# Control_Panel_Power.net
KiCad netlist of a schematic drawn in Altium Designer
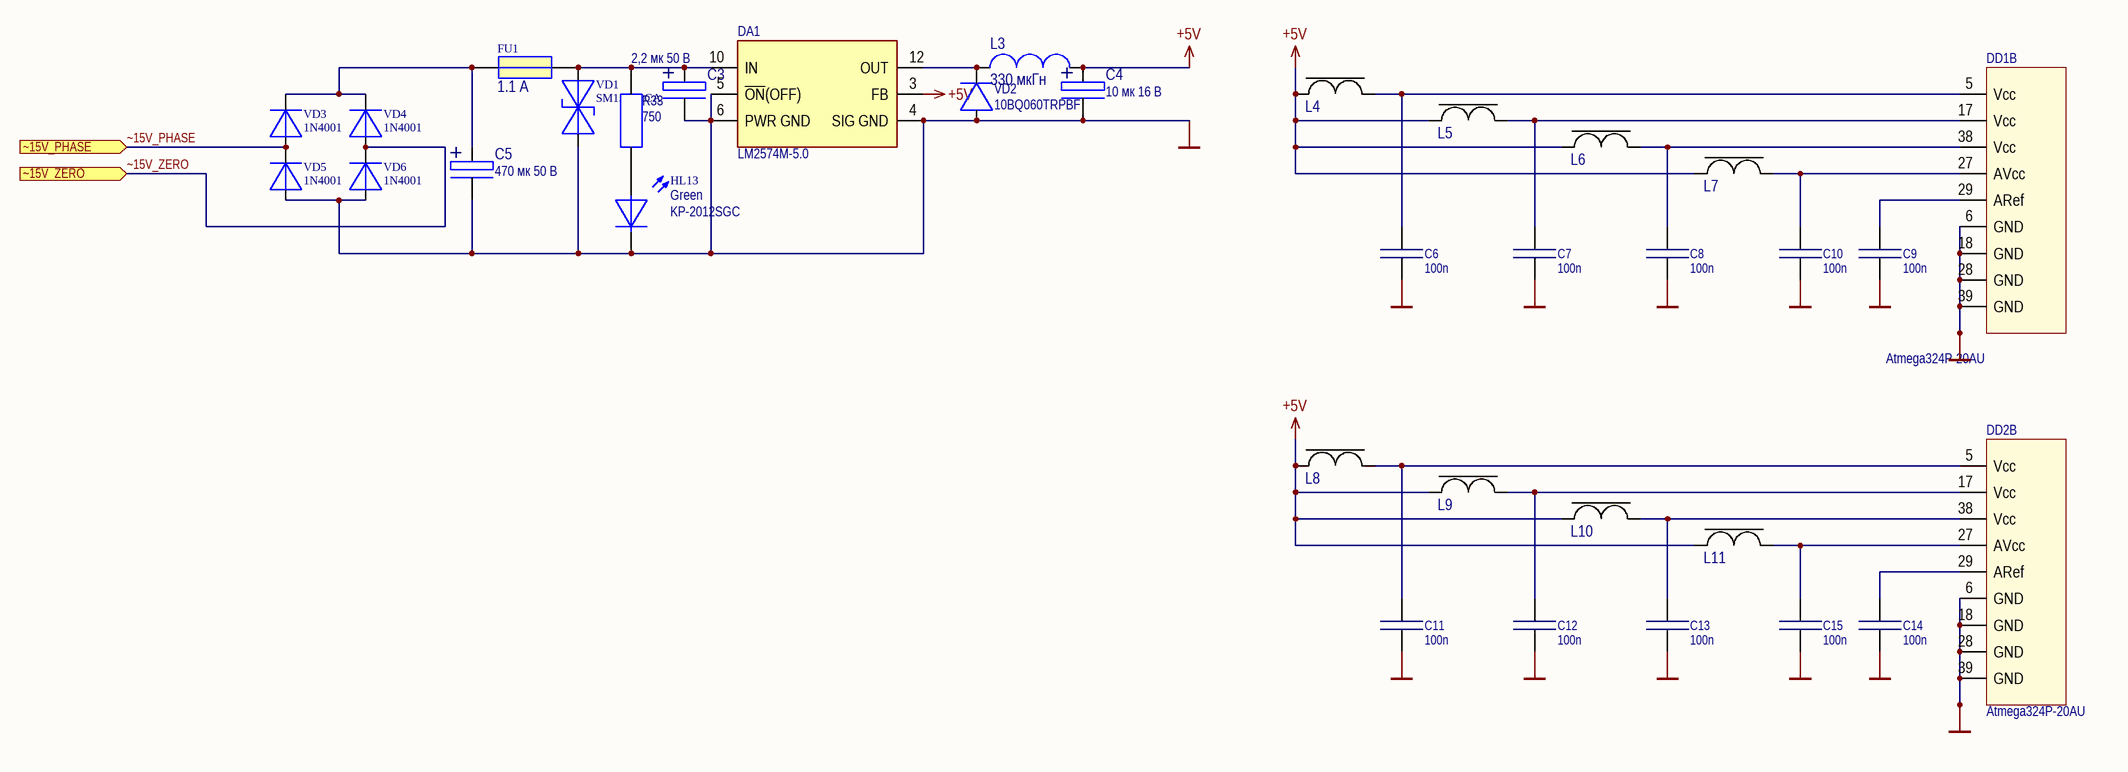
[diagram p0: Control_Panel_Power.SchDoc]

(export (version "E")
  (design (tool "Eeschema 10.0.6"))
  (components
    (comp (ref "C3")
      (value "2,2 мк 50 В")
      (footprint "Cap:CAP_POLAR_ELLYTE_B")
      (description "2,2uF 50V Polar capacitor")
      (fields
        (field (name "MANUFACTURERPARTNUMBER") "CA050M2R20REB-0405")
        (field (name "MANUFACTURER") "Yageo")
      )
      (libsource (lib "Cap") (part "02200_050"))
    )
    (comp (ref "C4")
      (value "10 мк 16 В")
      (footprint "Cap:CAP_POLAR_ELLYTE_B")
      (description "10uF 16V Polar SMD cap")
      (fields
        (field (name "MANUFACTURERPARTNUMBER") "CA016M0010REB-0405")
        (field (name "MANUFACTURER") "YAGEO")
      )
      (libsource (lib "Cap") (part "10000_016"))
    )
    (comp (ref "C5")
      (value "470 мк 50 В")
      (footprint "Cap:CAP_POLAR_10mm")
      (description "470uF 50V Polar capacitor")
      (fields (field (name "MANUFACTURERPARTNUMBER") "CA035M0220REG") (field (name "MANUFACTURER") "Yageo"))
      (libsource (lib "Cap") (part "470000_050"))
    )
    (comp (ref "C6")
      (value "100n")
      (footprint "SMDRC0805")
      (description "Generic capasitor non-polar")
      (fields (field (name "PARTNUMBER") "Capacitor 0805 100n"))
      (libsource (lib "library") (part "Capacitor"))
    )
    (comp (ref "C7")
      (value "100n")
      (footprint "SMDRC0805")
      (description "Generic capasitor non-polar")
      (fields (field (name "PARTNUMBER") "Capacitor 0805 100n"))
      (libsource (lib "library") (part "Capacitor"))
    )
    (comp (ref "C8")
      (value "100n")
      (footprint "SMDRC0805")
      (description "Generic capasitor non-polar")
      (fields (field (name "PARTNUMBER") "Capacitor 0805 100n"))
      (libsource (lib "library") (part "Capacitor"))
    )
    (comp (ref "C9")
      (value "100n")
      (footprint "SMDRC0805")
      (description "Generic capasitor non-polar")
      (fields (field (name "PARTNUMBER") "Capacitor 0805 100n"))
      (libsource (lib "library") (part "Capacitor"))
    )
    (comp (ref "C10")
      (value "100n")
      (footprint "SMDRC0805")
      (description "Generic capasitor non-polar")
      (fields (field (name "PARTNUMBER") "Capacitor 0805 100n"))
      (libsource (lib "library") (part "Capacitor"))
    )
    (comp (ref "C11")
      (value "100n")
      (footprint "SMDRC0805")
      (description "Generic capasitor non-polar")
      (fields (field (name "PARTNUMBER") "Capacitor 0805 100n"))
      (libsource (lib "library") (part "Capacitor"))
    )
    (comp (ref "C12")
      (value "100n")
      (footprint "SMDRC0805")
      (description "Generic capasitor non-polar")
      (fields (field (name "PARTNUMBER") "Capacitor 0805 100n"))
      (libsource (lib "library") (part "Capacitor"))
    )
    (comp (ref "C13")
      (value "100n")
      (footprint "SMDRC0805")
      (description "Generic capasitor non-polar")
      (fields (field (name "PARTNUMBER") "Capacitor 0805 100n"))
      (libsource (lib "library") (part "Capacitor"))
    )
    (comp (ref "C14")
      (value "100n")
      (footprint "SMDRC0805")
      (description "Generic capasitor non-polar")
      (fields (field (name "PARTNUMBER") "Capacitor 0805 100n"))
      (libsource (lib "library") (part "Capacitor"))
    )
    (comp (ref "C15")
      (value "100n")
      (footprint "SMDRC0805")
      (description "Generic capasitor non-polar")
      (fields (field (name "PARTNUMBER") "Capacitor 0805 100n"))
      (libsource (lib "library") (part "Capacitor"))
    )
    (comp (ref "DA1")
      (value "LM2574M-5.0")
      (footprint "Power:SOIC127P1030X264-14M")
      (fields (field (name "MANUFACTURERPARTNUMBER") "LM2574M-5.0"))
      (libsource (lib "Power") (part "LM2574M-5.0"))
    )
    (comp (ref "DD1")
      (value "Atmega324P-20AU")
      (footprint "Atmel Microcontroller 8-Bit Automotive AVR:44ML_M")
      (description "Microcontroller 8-bit")
      (fields (field (name "MANUFACTURER") "Atmel") (field (name "MANUFACTURERPARTNUMBER") "Atmega324P-20AU"))
      (libsource (lib "Microcontrollers") (part "Atmega324P-20AU"))
    )
    (comp (ref "DD2")
      (value "Atmega324P-20AU")
      (footprint "Atmel Microcontroller 8-Bit Automotive AVR:44ML_M")
      (description "Microcontroller 8-bit")
      (fields (field (name "MANUFACTURER") "Atmel") (field (name "MANUFACTURERPARTNUMBER") "Atmega324P-20AU"))
      (libsource (lib "Microcontrollers") (part "Atmega324P-20AU"))
    )
    (comp (ref "FU1")
      (value "1.1 А")
      (footprint "Power:EFuse 1.1A")
      (description "Fuse")
      (fields (field (name "MANUFACTURERPARTNUMBER") "EFuse LP60-110F"))
      (libsource (lib "Power") (part "EFuse LP60-110F"))
    )
    (comp (ref "HL13")
      (value "Green")
      (footprint "Indicator:DIOMELF2012M")
      (description "Diod LED SMD Green")
      (fields (field (name "MANUFACTURERPARTNUMBER") "KP-2012SGC"))
      (libsource (lib "Indicator") (part "LED1_G"))
    )
    (comp (ref "L3")
      (value "330 мкГн")
      (footprint "Inductor:INDP7972X50M")
      (description "Inductor")
      (fields (field (name "MANUFACTURERPARTNUMBER") "SCD0705T-331K-N"))
      (libsource (lib "Inductor") (part "SCD0705T-331K-N"))
    )
    (comp (ref "L4")
      (value "MPZ1608S181A")
      (footprint "Inductor:INDC0603X03M")
      (description "Ferrite Bead")
      (libsource (lib "Inductor") (part "Ferrite Bead"))
    )
    (comp (ref "L5")
      (value "MPZ1608S181A")
      (footprint "Inductor:INDC0603X03M")
      (description "Ferrite Bead")
      (libsource (lib "Inductor") (part "Ferrite Bead"))
    )
    (comp (ref "L6")
      (value "MPZ1608S181A")
      (footprint "Inductor:INDC0603X03M")
      (description "Ferrite Bead")
      (libsource (lib "Inductor") (part "Ferrite Bead"))
    )
    (comp (ref "L7")
      (value "MPZ1608S181A")
      (footprint "Inductor:INDC0603X03M")
      (description "Ferrite Bead")
      (libsource (lib "Inductor") (part "Ferrite Bead"))
    )
    (comp (ref "L8")
      (value "MPZ1608S181A")
      (footprint "Inductor:INDC0603X03M")
      (description "Ferrite Bead")
      (libsource (lib "Inductor") (part "Ferrite Bead"))
    )
    (comp (ref "L9")
      (value "MPZ1608S181A")
      (footprint "Inductor:INDC0603X03M")
      (description "Ferrite Bead")
      (libsource (lib "Inductor") (part "Ferrite Bead"))
    )
    (comp (ref "L10")
      (value "MPZ1608S181A")
      (footprint "Inductor:INDC0603X03M")
      (description "Ferrite Bead")
      (libsource (lib "Inductor") (part "Ferrite Bead"))
    )
    (comp (ref "L11")
      (value "MPZ1608S181A")
      (footprint "Inductor:INDC0603X03M")
      (description "Ferrite Bead")
      (libsource (lib "Inductor") (part "Ferrite Bead"))
    )
    (comp (ref "R33")
      (value "750")
      (footprint "SMDRC0805")
      (description "Generic resistor")
      (fields (field (name "PARTNUMBER") "Resistor 0805 750"))
      (libsource (lib "library") (part "Resistor"))
    )
    (comp (ref "VD1")
      (value "SM15T12CA")
      (footprint "DIod:SUPRES3216X18N")
      (description "Diod suppressor")
      (fields
        (field (name "MANUFACTURER") "ST Microelectronics")
        (field (name "MANUFACTURERPARTNUMBER") "SM15T12CA")
      )
      (libsource (lib "Diod") (part "SM15T12CA"))
    )
    (comp (ref "VD2")
      (value "10BQ060TRPBF")
      (footprint "DIod:SHOTKY 4.1x3.3")
      (description "DIODE SCHOTTKY 60V 1A DO214AA")
      (fields
        (field (name "MANUFACTURER") "Vishay Semiconductor Diodes Division")
        (field (name "MANUFACTURERPARTNUMBER") "10BQ060TRPBF")
      )
      (libsource (lib "Diod") (part "10BQ060TRPBF"))
    )
    (comp (ref "VD3")
      (value "1N4001")
      (footprint "DIod:PinDiode")
      (description "Rectifying diode")
      (fields (field (name "MANUFACTURERPARTNUMBER") "1N4001"))
      (libsource (lib "Diod") (part "1N4001"))
    )
    (comp (ref "VD4")
      (value "1N4001")
      (footprint "DIod:PinDiode")
      (description "Rectifying diode")
      (fields (field (name "MANUFACTURERPARTNUMBER") "1N4001"))
      (libsource (lib "Diod") (part "1N4001"))
    )
    (comp (ref "VD5")
      (value "1N4001")
      (footprint "DIod:PinDiode")
      (description "Rectifying diode")
      (fields (field (name "MANUFACTURERPARTNUMBER") "1N4001"))
      (libsource (lib "Diod") (part "1N4001"))
    )
    (comp (ref "VD6")
      (value "1N4001")
      (footprint "DIod:PinDiode")
      (description "Rectifying diode")
      (fields (field (name "MANUFACTURERPARTNUMBER") "1N4001"))
      (libsource (lib "Diod") (part "1N4001"))
    )
  )
  (nets
    (net (code "1") (name "+5V") (class "Default")
      (node (ref "C4") (pin "2") (pinfunction "+_2") (pintype "passive"))
      (node (ref "DA1") (pin "3") (pinfunction "FB_3") (pintype "passive"))
      (node (ref "L10") (pin "1") (pinfunction "1_1") (pintype "passive"))
      (node (ref "L11") (pin "1") (pinfunction "1_1") (pintype "passive"))
      (node (ref "L3") (pin "1") (pinfunction "1_1") (pintype "passive"))
      (node (ref "L4") (pin "1") (pinfunction "1_1") (pintype "passive"))
      (node (ref "L5") (pin "1") (pinfunction "1_1") (pintype "passive"))
      (node (ref "L6") (pin "1") (pinfunction "1_1") (pintype "passive"))
      (node (ref "L7") (pin "1") (pinfunction "1_1") (pintype "passive"))
      (node (ref "L8") (pin "1") (pinfunction "1_1") (pintype "passive"))
      (node (ref "L9") (pin "1") (pinfunction "1_1") (pintype "passive"))
    )
    (net (code "2") (name "/~15V_PHASE") (class "Default")
      (node (ref "VD3") (pin "A") (pinfunction "A_A") (pintype "passive"))
      (node (ref "VD5") (pin "K") (pinfunction "K_K") (pintype "passive"))
    )
    (net (code "3") (name "/~15V_ZERO") (class "Default")
      (node (ref "VD4") (pin "A") (pinfunction "A_A") (pintype "passive"))
      (node (ref "VD6") (pin "K") (pinfunction "K_K") (pintype "passive"))
    )
    (net (code "4") (name "GND") (class "Default")
      (node (ref "C10") (pin "1") (pintype "passive"))
      (node (ref "C11") (pin "2") (pintype "passive"))
      (node (ref "C12") (pin "2") (pintype "passive"))
      (node (ref "C13") (pin "2") (pintype "passive"))
      (node (ref "C14") (pin "2") (pintype "passive"))
      (node (ref "C15") (pin "1") (pintype "passive"))
      (node (ref "C3") (pin "1") (pinfunction "-_1") (pintype "passive"))
      (node (ref "C4") (pin "1") (pinfunction "-_1") (pintype "passive"))
      (node (ref "C5") (pin "1") (pinfunction "-_1") (pintype "passive"))
      (node (ref "C6") (pin "2") (pintype "passive"))
      (node (ref "C7") (pin "2") (pintype "passive"))
      (node (ref "C8") (pin "2") (pintype "passive"))
      (node (ref "C9") (pin "2") (pintype "passive"))
      (node (ref "DA1") (pin "4") (pinfunction "SIG_GND_4") (pintype "passive"))
      (node (ref "DA1") (pin "5") (pinfunction "~{ON}(OFF)_5") (pintype "passive"))
      (node (ref "DA1") (pin "6") (pinfunction "PWR_GND_6") (pintype "passive"))
      (node (ref "DD1") (pin "18") (pinfunction "GND_18") (pintype "power_in"))
      (node (ref "DD1") (pin "28") (pinfunction "GND_28") (pintype "power_in"))
      (node (ref "DD1") (pin "39") (pinfunction "GND_39") (pintype "power_in"))
      (node (ref "DD1") (pin "6") (pinfunction "GND_6") (pintype "power_in"))
      (node (ref "DD2") (pin "18") (pinfunction "GND_18") (pintype "power_in"))
      (node (ref "DD2") (pin "28") (pinfunction "GND_28") (pintype "power_in"))
      (node (ref "DD2") (pin "39") (pinfunction "GND_39") (pintype "power_in"))
      (node (ref "DD2") (pin "6") (pinfunction "GND_6") (pintype "power_in"))
      (node (ref "HL13") (pin "2") (pinfunction "2_2") (pintype "passive"))
      (node (ref "VD1") (pin "1") (pinfunction "1_1") (pintype "passive"))
      (node (ref "VD2") (pin "A") (pinfunction "A_A") (pintype "passive"))
      (node (ref "VD5") (pin "A") (pinfunction "A_A") (pintype "passive"))
      (node (ref "VD6") (pin "A") (pinfunction "A_A") (pintype "passive"))
    )
    (net (code "5") (name "Net-(C3-+)") (class "Default")
      (node (ref "C3") (pin "2") (pinfunction "+_2") (pintype "passive"))
      (node (ref "DA1") (pin "10") (pinfunction "IN_10") (pintype "passive"))
      (node (ref "FU1") (pin "2") (pinfunction "2_2") (pintype "passive"))
      (node (ref "R33") (pin "2") (pinfunction "2_2") (pintype "passive"))
      (node (ref "VD1") (pin "2") (pinfunction "2_2") (pintype "passive"))
    )
    (net (code "6") (name "Net-(C5-+)") (class "Default")
      (node (ref "C5") (pin "2") (pinfunction "+_2") (pintype "passive"))
      (node (ref "FU1") (pin "1") (pinfunction "1_1") (pintype "passive"))
      (node (ref "VD3") (pin "K") (pinfunction "K_K") (pintype "passive"))
      (node (ref "VD4") (pin "K") (pinfunction "K_K") (pintype "passive"))
    )
    (net (code "7") (name "Net-(C6-Pad1)") (class "Default")
      (node (ref "C6") (pin "1") (pintype "passive"))
      (node (ref "DD1") (pin "5") (pinfunction "Vcc_5") (pintype "power_in"))
      (node (ref "L4") (pin "2") (pinfunction "2_2") (pintype "passive"))
    )
    (net (code "8") (name "Net-(C7-Pad1)") (class "Default")
      (node (ref "C7") (pin "1") (pintype "passive"))
      (node (ref "DD1") (pin "17") (pinfunction "Vcc_17") (pintype "power_in"))
      (node (ref "L5") (pin "2") (pinfunction "2_2") (pintype "passive"))
    )
    (net (code "9") (name "Net-(C8-Pad1)") (class "Default")
      (node (ref "C8") (pin "1") (pintype "passive"))
      (node (ref "DD1") (pin "38") (pinfunction "Vcc_38") (pintype "power_in"))
      (node (ref "L6") (pin "2") (pinfunction "2_2") (pintype "passive"))
    )
    (net (code "10") (name "Net-(C11-Pad1)") (class "Default")
      (node (ref "C11") (pin "1") (pintype "passive"))
      (node (ref "DD2") (pin "5") (pinfunction "Vcc_5") (pintype "power_in"))
      (node (ref "L8") (pin "2") (pinfunction "2_2") (pintype "passive"))
    )
    (net (code "11") (name "Net-(C12-Pad1)") (class "Default")
      (node (ref "C12") (pin "1") (pintype "passive"))
      (node (ref "DD2") (pin "17") (pinfunction "Vcc_17") (pintype "power_in"))
      (node (ref "L9") (pin "2") (pinfunction "2_2") (pintype "passive"))
    )
    (net (code "12") (name "Net-(C13-Pad1)") (class "Default")
      (node (ref "C13") (pin "1") (pintype "passive"))
      (node (ref "DD2") (pin "38") (pinfunction "Vcc_38") (pintype "power_in"))
      (node (ref "L10") (pin "2") (pinfunction "2_2") (pintype "passive"))
    )
    (net (code "13") (name "Net-(DA1-OUT)") (class "Default")
      (node (ref "DA1") (pin "12") (pinfunction "OUT_12") (pintype "passive"))
      (node (ref "L3") (pin "2") (pinfunction "2_2") (pintype "passive"))
      (node (ref "VD2") (pin "K") (pinfunction "K_K") (pintype "passive"))
    )
    (net (code "14") (name "Net-(DD1B-ARef)") (class "Default")
      (node (ref "C9") (pin "1") (pintype "passive"))
      (node (ref "DD1") (pin "29") (pinfunction "ARef_29") (pintype "power_in"))
    )
    (net (code "15") (name "Net-(DD1B-AVcc)") (class "Default")
      (node (ref "C10") (pin "2") (pintype "passive"))
      (node (ref "DD1") (pin "27") (pinfunction "AVcc_27") (pintype "power_in"))
      (node (ref "L7") (pin "2") (pinfunction "2_2") (pintype "passive"))
    )
    (net (code "16") (name "Net-(DD2B-ARef)") (class "Default")
      (node (ref "C14") (pin "1") (pintype "passive"))
      (node (ref "DD2") (pin "29") (pinfunction "ARef_29") (pintype "power_in"))
    )
    (net (code "17") (name "Net-(DD2B-AVcc)") (class "Default")
      (node (ref "C15") (pin "2") (pintype "passive"))
      (node (ref "DD2") (pin "27") (pinfunction "AVcc_27") (pintype "power_in"))
      (node (ref "L11") (pin "2") (pinfunction "2_2") (pintype "passive"))
    )
    (net (code "18") (name "Net-(HL13-Pad1)") (class "Default")
      (node (ref "HL13") (pin "1") (pinfunction "1_1") (pintype "passive"))
      (node (ref "R33") (pin "1") (pinfunction "1_1") (pintype "passive"))
    )
  )
)
